# Schematic.net
KiCad netlist of a schematic drawn in Altium Designer
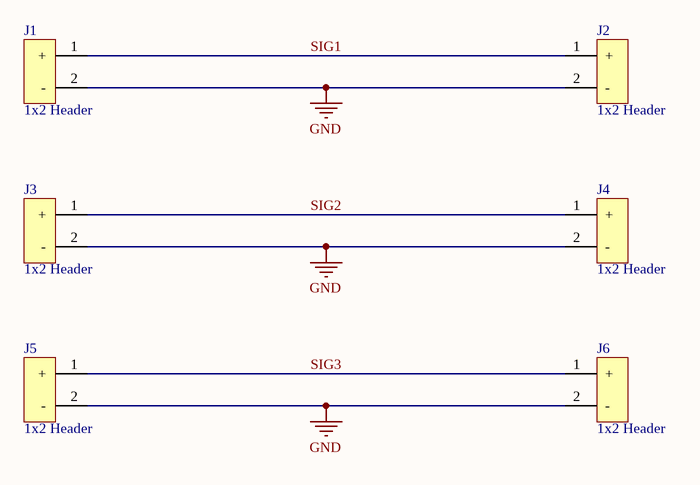
[diagram p0: Schematic.SchDoc]

(export (version "E")
  (design (tool "Eeschema 10.0.6"))
  (components
    (comp (ref "J1")
      (value "1x2 Header")
      (footprint "HDR1X2")
      (description "Headers & Wire Housings 2 PIN F/LK HEADER")
      (fields (field (name "MANUFACTURER") "Molex") (field (name "MANUFACTURER PART NUMBER") "22-29-2021"))
      (libsource (lib "Schlib") (part "22-29-2021"))
    )
    (comp (ref "J2")
      (value "1x2 Header")
      (footprint "HDR1X2")
      (description "Headers & Wire Housings 2 PIN F/LK HEADER")
      (fields (field (name "MANUFACTURER") "Molex") (field (name "MANUFACTURER PART NUMBER") "22-29-2021"))
      (libsource (lib "") (part "22-29-2021_1"))
    )
    (comp (ref "J3")
      (value "1x2 Header")
      (footprint "HDR1X2")
      (description "Headers & Wire Housings 2 PIN F/LK HEADER")
      (fields (field (name "MANUFACTURER") "Molex") (field (name "MANUFACTURER PART NUMBER") "22-29-2021"))
      (libsource (lib "Schlib") (part "22-29-2021"))
    )
    (comp (ref "J4")
      (value "1x2 Header")
      (footprint "HDR1X2")
      (description "Headers & Wire Housings 2 PIN F/LK HEADER")
      (fields (field (name "MANUFACTURER") "Molex") (field (name "MANUFACTURER PART NUMBER") "22-29-2021"))
      (libsource (lib "") (part "22-29-2021_1"))
    )
    (comp (ref "J5")
      (value "1x2 Header")
      (footprint "HDR1X2")
      (description "Headers & Wire Housings 2 PIN F/LK HEADER")
      (fields (field (name "MANUFACTURER") "Molex") (field (name "MANUFACTURER PART NUMBER") "22-29-2021"))
      (libsource (lib "Schlib") (part "22-29-2021"))
    )
    (comp (ref "J6")
      (value "1x2 Header")
      (footprint "HDR1X2")
      (description "Headers & Wire Housings 2 PIN F/LK HEADER")
      (fields (field (name "MANUFACTURER") "Molex") (field (name "MANUFACTURER PART NUMBER") "22-29-2021"))
      (libsource (lib "") (part "22-29-2021_1"))
    )
  )
  (nets
    (net (code "1") (name "/SIG1") (class "Default")
      (node (ref "J1") (pin "1") (pinfunction "+_1") (pintype "passive"))
      (node (ref "J2") (pin "1") (pinfunction "+_1") (pintype "passive"))
    )
    (net (code "2") (name "/SIG2") (class "Default")
      (node (ref "J3") (pin "1") (pinfunction "+_1") (pintype "passive"))
      (node (ref "J4") (pin "1") (pinfunction "+_1") (pintype "passive"))
    )
    (net (code "3") (name "/SIG3") (class "Default")
      (node (ref "J5") (pin "1") (pinfunction "+_1") (pintype "passive"))
      (node (ref "J6") (pin "1") (pinfunction "+_1") (pintype "passive"))
    )
    (net (code "4") (name "GND") (class "Default")
      (node (ref "J1") (pin "2") (pinfunction "-_2") (pintype "passive"))
      (node (ref "J2") (pin "2") (pinfunction "-_2") (pintype "passive"))
      (node (ref "J3") (pin "2") (pinfunction "-_2") (pintype "passive"))
      (node (ref "J4") (pin "2") (pinfunction "-_2") (pintype "passive"))
      (node (ref "J5") (pin "2") (pinfunction "-_2") (pintype "passive"))
      (node (ref "J6") (pin "2") (pinfunction "-_2") (pintype "passive"))
    )
  )
)
